# StepperDriver_Rev2.net
KiCad netlist of a schematic drawn in EAGLE
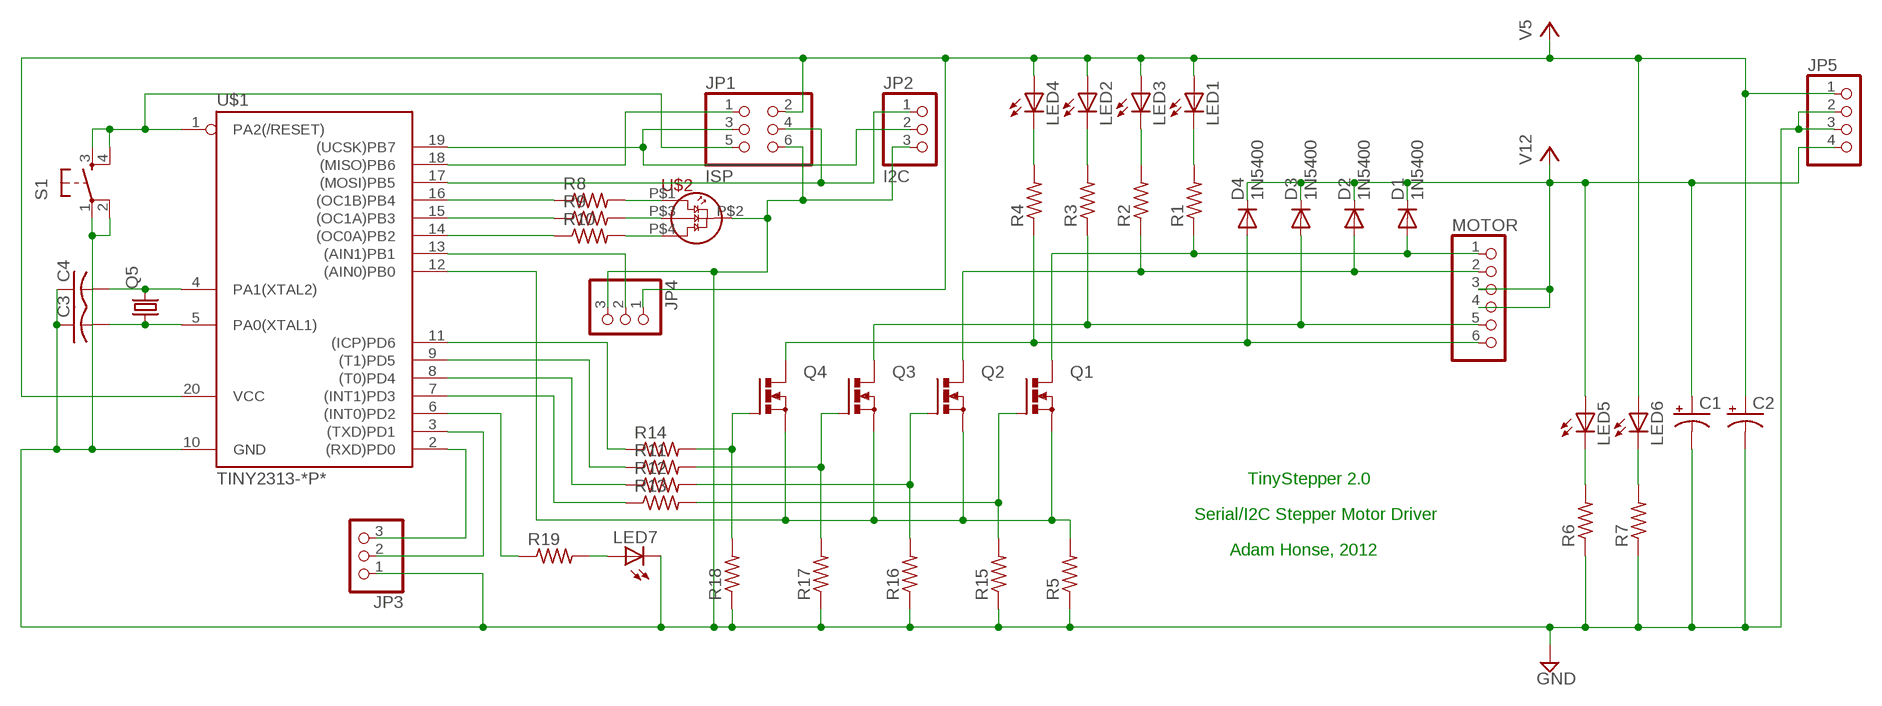
[diagram p0: schematic, sheet 1]

(export (version "E")
  (design (tool "Eeschema 10.0.6"))
  (components
    (comp (ref "C1")
      (value "CPOL-USE7.5-16")
      (footprint "eagle-import:E7,5-16")
      (libsource (lib "eagle-import") (part "CPOL-USE7.5-16"))
    )
    (comp (ref "C2")
      (value "CPOL-USE7.5-16")
      (footprint "eagle-import:E7,5-16")
      (libsource (lib "eagle-import") (part "CPOL-USE7.5-16"))
    )
    (comp (ref "C3")
      (value "C-US025-024X044")
      (footprint "eagle-import:C025-024X044")
      (libsource (lib "eagle-import") (part "C-US025-024X044"))
    )
    (comp (ref "C4")
      (value "C-US025-024X044")
      (footprint "eagle-import:C025-024X044")
      (libsource (lib "eagle-import") (part "C-US025-024X044"))
    )
    (comp (ref "D1")
      (value "1N5400")
      (footprint "eagle-import:DO201-15")
      (libsource (lib "eagle-import") (part "1N5400"))
    )
    (comp (ref "D2")
      (value "1N5400")
      (footprint "eagle-import:DO201-15")
      (libsource (lib "eagle-import") (part "1N5400"))
    )
    (comp (ref "D3")
      (value "1N5400")
      (footprint "eagle-import:DO201-15")
      (libsource (lib "eagle-import") (part "1N5400"))
    )
    (comp (ref "D4")
      (value "1N5400")
      (footprint "eagle-import:DO201-15")
      (libsource (lib "eagle-import") (part "1N5400"))
    )
    (comp (ref "JP1")
      (value "ISP")
      (footprint "eagle-import:2X03")
      (libsource (lib "eagle-import") (part "PINHD-2X3"))
    )
    (comp (ref "JP2")
      (value "I2C")
      (footprint "eagle-import:1X03")
      (libsource (lib "eagle-import") (part "PINHD-1X3"))
    )
    (comp (ref "JP3")
      (value "PINHD-1X3")
      (footprint "eagle-import:1X03")
      (libsource (lib "eagle-import") (part "PINHD-1X3"))
    )
    (comp (ref "JP4")
      (value "PINHD-1X3")
      (footprint "eagle-import:1X03")
      (libsource (lib "eagle-import") (part "PINHD-1X3"))
    )
    (comp (ref "JP5")
      (value "PINHD-1X4")
      (footprint "eagle-import:1X04")
      (libsource (lib "eagle-import") (part "PINHD-1X4"))
    )
    (comp (ref "LED1")
      (value "LED5MM")
      (footprint "eagle-import:LED5MM")
      (libsource (lib "eagle-import") (part "LED5MM"))
    )
    (comp (ref "LED2")
      (value "LED5MM")
      (footprint "eagle-import:LED5MM")
      (libsource (lib "eagle-import") (part "LED5MM"))
    )
    (comp (ref "LED3")
      (value "LED5MM")
      (footprint "eagle-import:LED5MM")
      (libsource (lib "eagle-import") (part "LED5MM"))
    )
    (comp (ref "LED4")
      (value "LED5MM")
      (footprint "eagle-import:LED5MM")
      (libsource (lib "eagle-import") (part "LED5MM"))
    )
    (comp (ref "LED5")
      (value "LED5MM")
      (footprint "eagle-import:LED5MM")
      (libsource (lib "eagle-import") (part "LED5MM"))
    )
    (comp (ref "LED6")
      (value "LED5MM")
      (footprint "eagle-import:LED5MM")
      (libsource (lib "eagle-import") (part "LED5MM"))
    )
    (comp (ref "LED7")
      (value "LED5MM")
      (footprint "eagle-import:LED5MM")
      (libsource (lib "eagle-import") (part "LED5MM"))
    )
    (comp (ref "MOTOR")
      (value "PINHD-1X6")
      (footprint "eagle-import:1X06")
      (libsource (lib "eagle-import") (part "PINHD-1X6"))
    )
    (comp (ref "Q1")
      (value "PMOSFET_NTO220BV")
      (footprint "eagle-import:TO220BV")
      (libsource (lib "eagle-import") (part "PMOSFET_NTO220BV"))
    )
    (comp (ref "Q2")
      (value "PMOSFET_NTO220BV")
      (footprint "eagle-import:TO220BV")
      (libsource (lib "eagle-import") (part "PMOSFET_NTO220BV"))
    )
    (comp (ref "Q3")
      (value "PMOSFET_NTO220BV")
      (footprint "eagle-import:TO220BV")
      (libsource (lib "eagle-import") (part "PMOSFET_NTO220BV"))
    )
    (comp (ref "Q4")
      (value "PMOSFET_NTO220BV")
      (footprint "eagle-import:TO220BV")
      (libsource (lib "eagle-import") (part "PMOSFET_NTO220BV"))
    )
    (comp (ref "Q5")
      (value "CRYSTALHC49U70")
      (footprint "eagle-import:HC49U70")
      (libsource (lib "eagle-import") (part "CRYSTALHC49U70"))
    )
    (comp (ref "R1")
      (value "R-US_0204/7")
      (footprint "eagle-import:0204_7")
      (libsource (lib "eagle-import") (part "R-US_0204/7"))
    )
    (comp (ref "R2")
      (value "R-US_0204/7")
      (footprint "eagle-import:0204_7")
      (libsource (lib "eagle-import") (part "R-US_0204/7"))
    )
    (comp (ref "R3")
      (value "R-US_0204/7")
      (footprint "eagle-import:0204_7")
      (libsource (lib "eagle-import") (part "R-US_0204/7"))
    )
    (comp (ref "R4")
      (value "R-US_0204/7")
      (footprint "eagle-import:0204_7")
      (libsource (lib "eagle-import") (part "R-US_0204/7"))
    )
    (comp (ref "R5")
      (value "R-US_0617/22")
      (footprint "eagle-import:0617_22")
      (libsource (lib "eagle-import") (part "R-US_0617/22"))
    )
    (comp (ref "R6")
      (value "R-US_0204/7")
      (footprint "eagle-import:0204_7")
      (libsource (lib "eagle-import") (part "R-US_0204/7"))
    )
    (comp (ref "R7")
      (value "R-US_0204/7")
      (footprint "eagle-import:0204_7")
      (libsource (lib "eagle-import") (part "R-US_0204/7"))
    )
    (comp (ref "R8")
      (value "R-US_0204/7")
      (footprint "eagle-import:0204_7")
      (libsource (lib "eagle-import") (part "R-US_0204/7"))
    )
    (comp (ref "R9")
      (value "R-US_0204/7")
      (footprint "eagle-import:0204_7")
      (libsource (lib "eagle-import") (part "R-US_0204/7"))
    )
    (comp (ref "R10")
      (value "R-US_0204/7")
      (footprint "eagle-import:0204_7")
      (libsource (lib "eagle-import") (part "R-US_0204/7"))
    )
    (comp (ref "R11")
      (value "R-US_0204/7")
      (footprint "eagle-import:0204_7")
      (libsource (lib "eagle-import") (part "R-US_0204/7"))
    )
    (comp (ref "R12")
      (value "R-US_0204/7")
      (footprint "eagle-import:0204_7")
      (libsource (lib "eagle-import") (part "R-US_0204/7"))
    )
    (comp (ref "R13")
      (value "R-US_0204/7")
      (footprint "eagle-import:0204_7")
      (libsource (lib "eagle-import") (part "R-US_0204/7"))
    )
    (comp (ref "R14")
      (value "R-US_0204/7")
      (footprint "eagle-import:0204_7")
      (libsource (lib "eagle-import") (part "R-US_0204/7"))
    )
    (comp (ref "R15")
      (value "R-US_0204/7")
      (footprint "eagle-import:0204_7")
      (libsource (lib "eagle-import") (part "R-US_0204/7"))
    )
    (comp (ref "R16")
      (value "R-US_0204/7")
      (footprint "eagle-import:0204_7")
      (libsource (lib "eagle-import") (part "R-US_0204/7"))
    )
    (comp (ref "R17")
      (value "R-US_0204/7")
      (footprint "eagle-import:0204_7")
      (libsource (lib "eagle-import") (part "R-US_0204/7"))
    )
    (comp (ref "R18")
      (value "R-US_0204/7")
      (footprint "eagle-import:0204_7")
      (libsource (lib "eagle-import") (part "R-US_0204/7"))
    )
    (comp (ref "R19")
      (value "R-US_0204/7")
      (footprint "eagle-import:0204_7")
      (libsource (lib "eagle-import") (part "R-US_0204/7"))
    )
    (comp (ref "S1")
      (value "TAC_SWITCHPTH")
      (footprint "eagle-import:TACTILE-PTH")
      (libsource (lib "eagle-import") (part "TAC_SWITCHPTH"))
    )
    (comp (ref "U$1")
      (value "TINY2313-*P*")
      (footprint "eagle-import:DIL20")
      (libsource (lib "eagle-import") (part "TINY2313-P"))
    )
    (comp (ref "U$2")
      (value "5MMRGBLED")
      (footprint "eagle-import:LED5MMRGB")
      (libsource (lib "eagle-import") (part "5MMRGBLED"))
    )
  )
  (nets
    (net (code "1") (name "GND") (class "Default")
      (node (ref "C1") (pin "-") (pinfunction "-_-") (pintype "passive"))
      (node (ref "C2") (pin "-") (pinfunction "-_-") (pintype "passive"))
      (node (ref "C3") (pin "1") (pinfunction "1_1") (pintype "passive"))
      (node (ref "C4") (pin "1") (pinfunction "1_1") (pintype "passive"))
      (node (ref "JP1") (pin "6") (pinfunction "6_6") (pintype "passive"))
      (node (ref "JP2") (pin "3") (pinfunction "3_3") (pintype "passive"))
      (node (ref "JP3") (pin "1") (pinfunction "1_1") (pintype "passive"))
      (node (ref "JP4") (pin "3") (pinfunction "3_3") (pintype "passive"))
      (node (ref "JP5") (pin "2") (pinfunction "2_2") (pintype "passive"))
      (node (ref "JP5") (pin "3") (pinfunction "3_3") (pintype "passive"))
      (node (ref "LED7") (pin "K") (pinfunction "C_K") (pintype "passive"))
      (node (ref "R15") (pin "1") (pinfunction "1_1") (pintype "passive"))
      (node (ref "R16") (pin "1") (pinfunction "1_1") (pintype "passive"))
      (node (ref "R17") (pin "1") (pinfunction "1_1") (pintype "passive"))
      (node (ref "R18") (pin "1") (pinfunction "1_1") (pintype "passive"))
      (node (ref "R5") (pin "1") (pinfunction "1_1") (pintype "passive"))
      (node (ref "R6") (pin "1") (pinfunction "1_1") (pintype "passive"))
      (node (ref "R7") (pin "1") (pinfunction "1_1") (pintype "passive"))
      (node (ref "S1") (pin "1") (pinfunction "1_1") (pintype "passive"))
      (node (ref "S1") (pin "2") (pinfunction "2_2") (pintype "passive"))
      (node (ref "U$1") (pin "10") (pinfunction "GND_10") (pintype "power_in"))
      (node (ref "U$2") (pin "P$2") (pinfunction "CATHODE_P$2") (pintype "bidirectional"))
    )
    (net (code "2") (name "Net-(D1-PadA)") (class "Default")
      (node (ref "D1") (pin "A") (pinfunction "A_A") (pintype "passive"))
      (node (ref "MOTOR") (pin "1") (pinfunction "1_1") (pintype "passive"))
      (node (ref "Q1") (pin "D") (pinfunction "D_D") (pintype "passive"))
      (node (ref "R1") (pin "1") (pinfunction "1_1") (pintype "passive"))
    )
    (net (code "3") (name "Net-(D2-PadA)") (class "Default")
      (node (ref "D2") (pin "A") (pinfunction "A_A") (pintype "passive"))
      (node (ref "MOTOR") (pin "2") (pinfunction "2_2") (pintype "passive"))
      (node (ref "Q2") (pin "D") (pinfunction "D_D") (pintype "passive"))
      (node (ref "R2") (pin "1") (pinfunction "1_1") (pintype "passive"))
    )
    (net (code "4") (name "Net-(D3-PadA)") (class "Default")
      (node (ref "D3") (pin "A") (pinfunction "A_A") (pintype "passive"))
      (node (ref "MOTOR") (pin "5") (pinfunction "5_5") (pintype "passive"))
      (node (ref "Q3") (pin "D") (pinfunction "D_D") (pintype "passive"))
      (node (ref "R3") (pin "1") (pinfunction "1_1") (pintype "passive"))
    )
    (net (code "5") (name "Net-(D4-PadA)") (class "Default")
      (node (ref "D4") (pin "A") (pinfunction "A_A") (pintype "passive"))
      (node (ref "MOTOR") (pin "6") (pinfunction "6_6") (pintype "passive"))
      (node (ref "Q4") (pin "D") (pinfunction "D_D") (pintype "passive"))
      (node (ref "R4") (pin "1") (pinfunction "1_1") (pintype "passive"))
    )
    (net (code "6") (name "Net-(LED1-C)") (class "Default")
      (node (ref "LED1") (pin "K") (pinfunction "C_K") (pintype "passive"))
      (node (ref "R1") (pin "2") (pinfunction "2_2") (pintype "passive"))
    )
    (net (code "7") (name "Net-(LED2-C)") (class "Default")
      (node (ref "LED2") (pin "K") (pinfunction "C_K") (pintype "passive"))
      (node (ref "R3") (pin "2") (pinfunction "2_2") (pintype "passive"))
    )
    (net (code "8") (name "Net-(LED3-C)") (class "Default")
      (node (ref "LED3") (pin "K") (pinfunction "C_K") (pintype "passive"))
      (node (ref "R2") (pin "2") (pinfunction "2_2") (pintype "passive"))
    )
    (net (code "9") (name "Net-(LED4-C)") (class "Default")
      (node (ref "LED4") (pin "K") (pinfunction "C_K") (pintype "passive"))
      (node (ref "R4") (pin "2") (pinfunction "2_2") (pintype "passive"))
    )
    (net (code "10") (name "Net-(LED5-C)") (class "Default")
      (node (ref "LED5") (pin "K") (pinfunction "C_K") (pintype "passive"))
      (node (ref "R6") (pin "2") (pinfunction "2_2") (pintype "passive"))
    )
    (net (code "11") (name "Net-(LED6-C)") (class "Default")
      (node (ref "LED6") (pin "K") (pinfunction "C_K") (pintype "passive"))
      (node (ref "R7") (pin "2") (pinfunction "2_2") (pintype "passive"))
    )
    (net (code "12") (name "Net-(LED7-PadA)") (class "Default")
      (node (ref "LED7") (pin "A") (pinfunction "A_A") (pintype "passive"))
      (node (ref "R19") (pin "2") (pinfunction "2_2") (pintype "passive"))
    )
    (net (code "13") (name "Net-(Q1-PadG)") (class "Default")
      (node (ref "Q1") (pin "G") (pinfunction "G_G") (pintype "passive"))
      (node (ref "R13") (pin "2") (pinfunction "2_2") (pintype "passive"))
      (node (ref "R15") (pin "2") (pinfunction "2_2") (pintype "passive"))
    )
    (net (code "14") (name "Net-(Q2-PadG)") (class "Default")
      (node (ref "Q2") (pin "G") (pinfunction "G_G") (pintype "passive"))
      (node (ref "R12") (pin "2") (pinfunction "2_2") (pintype "passive"))
      (node (ref "R16") (pin "2") (pinfunction "2_2") (pintype "passive"))
    )
    (net (code "15") (name "Net-(Q3-PadG)") (class "Default")
      (node (ref "Q3") (pin "G") (pinfunction "G_G") (pintype "passive"))
      (node (ref "R11") (pin "2") (pinfunction "2_2") (pintype "passive"))
      (node (ref "R17") (pin "2") (pinfunction "2_2") (pintype "passive"))
    )
    (net (code "16") (name "Net-(Q4-PadG)") (class "Default")
      (node (ref "Q4") (pin "G") (pinfunction "G_G") (pintype "passive"))
      (node (ref "R14") (pin "2") (pinfunction "2_2") (pintype "passive"))
      (node (ref "R18") (pin "2") (pinfunction "2_2") (pintype "passive"))
    )
    (net (code "17") (name "Net-(U$1-(AIN0)PB0)") (class "Default")
      (node (ref "Q1") (pin "S") (pinfunction "S_S") (pintype "passive"))
      (node (ref "Q2") (pin "S") (pinfunction "S_S") (pintype "passive"))
      (node (ref "Q3") (pin "S") (pinfunction "S_S") (pintype "passive"))
      (node (ref "Q4") (pin "S") (pinfunction "S_S") (pintype "passive"))
      (node (ref "R5") (pin "2") (pinfunction "2_2") (pintype "passive"))
      (node (ref "U$1") (pin "12") (pinfunction "(AIN0)PB0_12") (pintype "bidirectional"))
    )
    (net (code "18") (name "Net-(U$1-(AIN1)PB1)") (class "Default")
      (node (ref "JP4") (pin "2") (pinfunction "2_2") (pintype "passive"))
      (node (ref "U$1") (pin "13") (pinfunction "(AIN1)PB1_13") (pintype "bidirectional"))
    )
    (net (code "19") (name "Net-(U$1-(ICP)PD6)") (class "Default")
      (node (ref "R14") (pin "1") (pinfunction "1_1") (pintype "passive"))
      (node (ref "U$1") (pin "11") (pinfunction "(ICP)PD6_11") (pintype "bidirectional"))
    )
    (net (code "20") (name "Net-(U$1-(INT0)PD2)") (class "Default")
      (node (ref "R19") (pin "1") (pinfunction "1_1") (pintype "passive"))
      (node (ref "U$1") (pin "6") (pinfunction "(INT0)PD2_6") (pintype "bidirectional"))
    )
    (net (code "21") (name "Net-(U$1-(INT1)PD3)") (class "Default")
      (node (ref "R13") (pin "1") (pinfunction "1_1") (pintype "passive"))
      (node (ref "U$1") (pin "7") (pinfunction "(INT1)PD3_7") (pintype "bidirectional"))
    )
    (net (code "22") (name "Net-(U$1-(MISO)PB6)") (class "Default")
      (node (ref "JP1") (pin "1") (pinfunction "1_1") (pintype "passive"))
      (node (ref "U$1") (pin "18") (pinfunction "(MISO)PB6_18") (pintype "bidirectional"))
    )
    (net (code "23") (name "Net-(U$1-(MOSI)PB5)") (class "Default")
      (node (ref "JP1") (pin "4") (pinfunction "4_4") (pintype "passive"))
      (node (ref "JP2") (pin "1") (pinfunction "1_1") (pintype "passive"))
      (node (ref "U$1") (pin "17") (pinfunction "(MOSI)PB5_17") (pintype "bidirectional"))
    )
    (net (code "24") (name "Net-(U$1-(OC0A)PB2)") (class "Default")
      (node (ref "R10") (pin "1") (pinfunction "1_1") (pintype "passive"))
      (node (ref "U$1") (pin "14") (pinfunction "(OC0A)PB2_14") (pintype "bidirectional"))
    )
    (net (code "25") (name "Net-(U$1-(OC1A)PB3)") (class "Default")
      (node (ref "R9") (pin "1") (pinfunction "1_1") (pintype "passive"))
      (node (ref "U$1") (pin "15") (pinfunction "(OC1A)PB3_15") (pintype "bidirectional"))
    )
    (net (code "26") (name "Net-(U$1-(OC1B)PB4)") (class "Default")
      (node (ref "R8") (pin "1") (pinfunction "1_1") (pintype "passive"))
      (node (ref "U$1") (pin "16") (pinfunction "(OC1B)PB4_16") (pintype "bidirectional"))
    )
    (net (code "27") (name "Net-(U$1-(RXD)PD0)") (class "Default")
      (node (ref "JP3") (pin "3") (pinfunction "3_3") (pintype "passive"))
      (node (ref "U$1") (pin "2") (pinfunction "(RXD)PD0_2") (pintype "bidirectional"))
    )
    (net (code "28") (name "Net-(U$1-(T0)PD4)") (class "Default")
      (node (ref "R12") (pin "1") (pinfunction "1_1") (pintype "passive"))
      (node (ref "U$1") (pin "8") (pinfunction "(T0)PD4_8") (pintype "bidirectional"))
    )
    (net (code "29") (name "Net-(U$1-(T1)PD5)") (class "Default")
      (node (ref "R11") (pin "1") (pinfunction "1_1") (pintype "passive"))
      (node (ref "U$1") (pin "9") (pinfunction "(T1)PD5_9") (pintype "bidirectional"))
    )
    (net (code "30") (name "Net-(U$1-(TXD)PD1)") (class "Default")
      (node (ref "JP3") (pin "2") (pinfunction "2_2") (pintype "passive"))
      (node (ref "U$1") (pin "3") (pinfunction "(TXD)PD1_3") (pintype "bidirectional"))
    )
    (net (code "31") (name "Net-(U$1-(UCSK)PB7)") (class "Default")
      (node (ref "JP1") (pin "3") (pinfunction "3_3") (pintype "passive"))
      (node (ref "JP2") (pin "2") (pinfunction "2_2") (pintype "passive"))
      (node (ref "U$1") (pin "19") (pinfunction "(UCSK)PB7_19") (pintype "bidirectional"))
    )
    (net (code "32") (name "Net-(U$1-PA0(XTAL1))") (class "Default")
      (node (ref "C3") (pin "2") (pinfunction "2_2") (pintype "passive"))
      (node (ref "Q5") (pin "1") (pinfunction "1_1") (pintype "passive"))
      (node (ref "U$1") (pin "5") (pinfunction "PA0(XTAL1)_5") (pintype "bidirectional"))
    )
    (net (code "33") (name "Net-(U$1-PA1(XTAL2))") (class "Default")
      (node (ref "C4") (pin "2") (pinfunction "2_2") (pintype "passive"))
      (node (ref "Q5") (pin "2") (pinfunction "2_2") (pintype "passive"))
      (node (ref "U$1") (pin "4") (pinfunction "PA1(XTAL2)_4") (pintype "bidirectional"))
    )
    (net (code "34") (name "Net-(U$1-PA2({slash}RESET))") (class "Default")
      (node (ref "JP1") (pin "5") (pinfunction "5_5") (pintype "passive"))
      (node (ref "S1") (pin "3") (pinfunction "3_3") (pintype "passive"))
      (node (ref "S1") (pin "4") (pinfunction "4_4") (pintype "passive"))
      (node (ref "U$1") (pin "1") (pinfunction "PA2(/RESET)_1") (pintype "input"))
    )
    (net (code "35") (name "Net-(U$2-BLUE)") (class "Default")
      (node (ref "R10") (pin "2") (pinfunction "2_2") (pintype "passive"))
      (node (ref "U$2") (pin "P$4") (pinfunction "BLUE_P$4") (pintype "bidirectional"))
    )
    (net (code "36") (name "Net-(U$2-GREEN)") (class "Default")
      (node (ref "R9") (pin "2") (pinfunction "2_2") (pintype "passive"))
      (node (ref "U$2") (pin "P$3") (pinfunction "GREEN_P$3") (pintype "bidirectional"))
    )
    (net (code "37") (name "Net-(U$2-RED)") (class "Default")
      (node (ref "R8") (pin "2") (pinfunction "2_2") (pintype "passive"))
      (node (ref "U$2") (pin "P$1") (pinfunction "RED_P$1") (pintype "bidirectional"))
    )
    (net (code "38") (name "V5") (class "Default")
      (node (ref "C2") (pin "+") (pinfunction "+_+") (pintype "passive"))
      (node (ref "JP1") (pin "2") (pinfunction "2_2") (pintype "passive"))
      (node (ref "JP4") (pin "1") (pinfunction "1_1") (pintype "passive"))
      (node (ref "JP5") (pin "1") (pinfunction "1_1") (pintype "passive"))
      (node (ref "LED1") (pin "A") (pinfunction "A_A") (pintype "passive"))
      (node (ref "LED2") (pin "A") (pinfunction "A_A") (pintype "passive"))
      (node (ref "LED3") (pin "A") (pinfunction "A_A") (pintype "passive"))
      (node (ref "LED4") (pin "A") (pinfunction "A_A") (pintype "passive"))
      (node (ref "LED6") (pin "A") (pinfunction "A_A") (pintype "passive"))
      (node (ref "U$1") (pin "20") (pinfunction "VCC_20") (pintype "power_in"))
    )
    (net (code "39") (name "V12") (class "Default")
      (node (ref "C1") (pin "+") (pinfunction "+_+") (pintype "passive"))
      (node (ref "D1") (pin "C") (pinfunction "C_C") (pintype "passive"))
      (node (ref "D2") (pin "C") (pinfunction "C_C") (pintype "passive"))
      (node (ref "D3") (pin "C") (pinfunction "C_C") (pintype "passive"))
      (node (ref "D4") (pin "C") (pinfunction "C_C") (pintype "passive"))
      (node (ref "JP5") (pin "4") (pinfunction "4_4") (pintype "passive"))
      (node (ref "LED5") (pin "A") (pinfunction "A_A") (pintype "passive"))
      (node (ref "MOTOR") (pin "3") (pinfunction "3_3") (pintype "passive"))
      (node (ref "MOTOR") (pin "4") (pinfunction "4_4") (pintype "passive"))
    )
  )
)
